# WatchDog.net
KiCad netlist of a schematic drawn in EAGLE
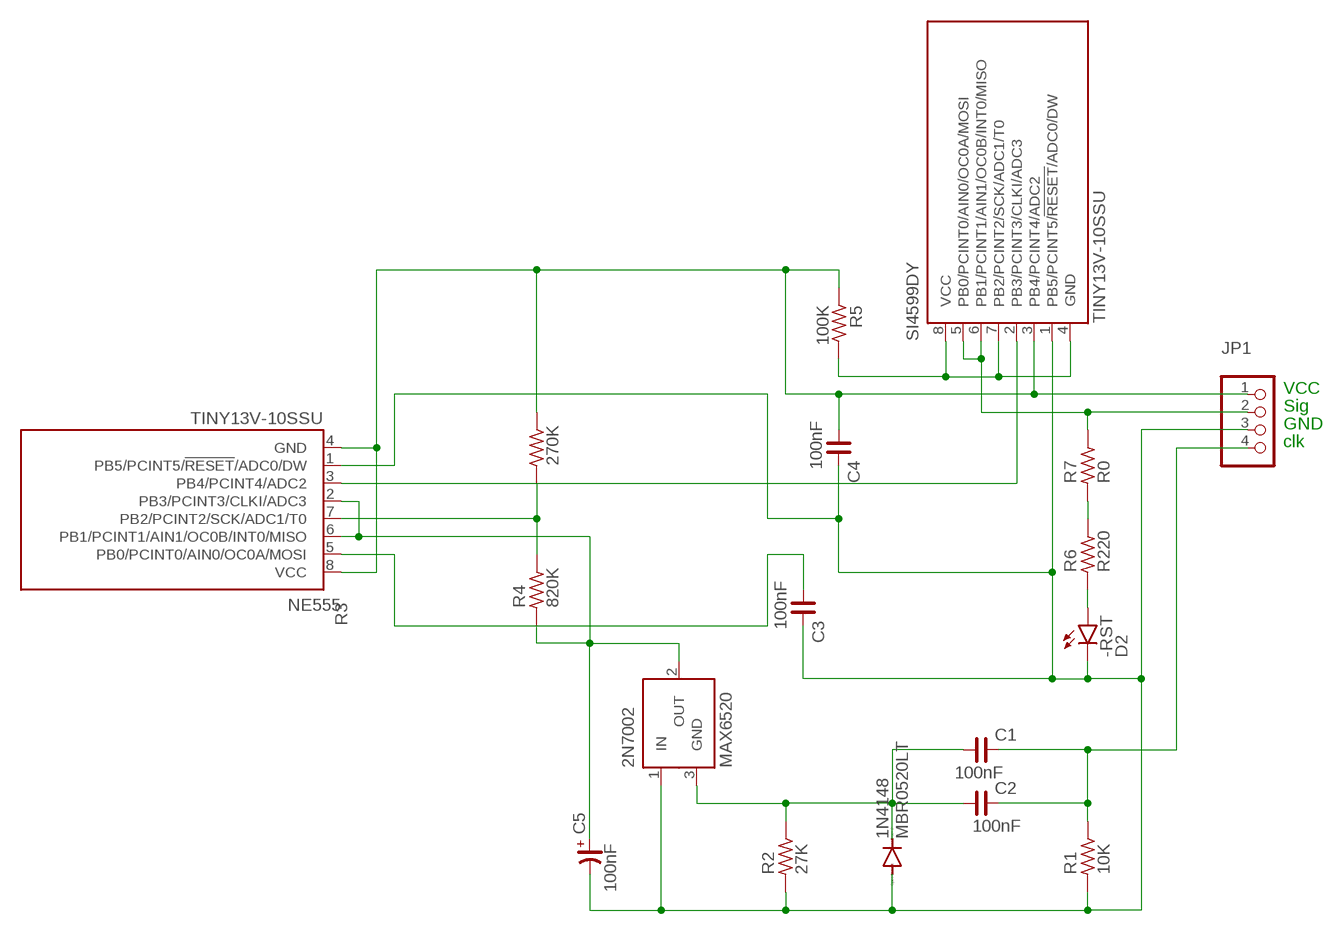
[diagram p0: schematic, sheet 1]

(export (version "E")
  (design (tool "Eeschema 10.0.6"))
  (components
    (comp (ref "-RST")
      (value "D2")
      (footprint "eagle-import:SML0603")
      (libsource (lib "eagle-import") (part "LEDSML0603"))
    )
    (comp (ref "1N4148")
      (value "MBR0520LT")
      (footprint "eagle-import:SOD123")
      (libsource (lib "eagle-import") (part "MBR0520LT"))
    )
    (comp (ref "2N7002")
      (value "MAX6520")
      (footprint "eagle-import:SOT23")
      (fields (field (name "MF") "MAXIM") (field (name "MPN") "MAX6520EUR-T"))
      (libsource (lib "eagle-import") (part "MAX6520"))
    )
    (comp (ref "C1")
      (value "100nF")
      (footprint "eagle-import:C0603")
      (libsource (lib "eagle-import") (part "C_0603"))
    )
    (comp (ref "C2")
      (value "100nF")
      (footprint "eagle-import:C0603")
      (libsource (lib "eagle-import") (part "C_0603"))
    )
    (comp (ref "C3")
      (value "100nF")
      (footprint "eagle-import:C0603")
      (libsource (lib "eagle-import") (part "C_0603"))
    )
    (comp (ref "C4")
      (value "100nF")
      (footprint "eagle-import:C0603")
      (libsource (lib "eagle-import") (part "C_0603"))
    )
    (comp (ref "C5")
      (value "100nF")
      (footprint "eagle-import:CSV-E_F")
      (libsource (lib "eagle-import") (part "CP_SV-E/F"))
    )
    (comp (ref "JP1")
      (value "PINHD-1X4")
      (footprint "eagle-import:1X04")
      (libsource (lib "eagle-import") (part "PINHD-1X4"))
    )
    (comp (ref "NE555")
      (value "TINY13V-10SSU")
      (footprint "eagle-import:8S1")
      (fields (field (name "MPN") "ATTINY13V-10SSU"))
      (libsource (lib "eagle-import") (part "TINY13SSUV-10"))
    )
    (comp (ref "R1")
      (value "10K")
      (footprint "eagle-import:R0603")
      (libsource (lib "eagle-import") (part "R_0603"))
    )
    (comp (ref "R2")
      (value "27K")
      (footprint "eagle-import:R0603")
      (libsource (lib "eagle-import") (part "R_0603"))
    )
    (comp (ref "R3")
      (value "270K")
      (footprint "eagle-import:R0603")
      (libsource (lib "eagle-import") (part "R_0603"))
    )
    (comp (ref "R4")
      (value "820K")
      (footprint "eagle-import:R0603")
      (libsource (lib "eagle-import") (part "R_0603"))
    )
    (comp (ref "R5")
      (value "100K")
      (footprint "eagle-import:R0603")
      (libsource (lib "eagle-import") (part "R_0603"))
    )
    (comp (ref "R6")
      (value "R220")
      (footprint "eagle-import:R0603")
      (libsource (lib "eagle-import") (part "R_0603"))
    )
    (comp (ref "R7")
      (value "R0")
      (footprint "eagle-import:R0402")
      (libsource (lib "eagle-import") (part "R_0402"))
    )
    (comp (ref "SI4599DY")
      (value "TINY13V-10SSU")
      (footprint "eagle-import:8S1")
      (fields (field (name "MPN") "ATTINY13V-10SSU"))
      (libsource (lib "eagle-import") (part "TINY13SSUV-10"))
    )
  )
  (nets
    (net (code "1") (name "Net-(-RST-PadA)") (class "Default")
      (node (ref "-RST") (pin "A") (pinfunction "A_A") (pintype "passive"))
      (node (ref "R6") (pin "1") (pinfunction "1_1") (pintype "passive"))
    )
    (net (code "2") (name "Net-(2N7002-GND)") (class "Default")
      (node (ref "1N4148") (pin "C") (pinfunction "C_C") (pintype "passive"))
      (node (ref "2N7002") (pin "3") (pinfunction "GND_3") (pintype "power_in"))
      (node (ref "C1") (pin "1") (pinfunction "1_1") (pintype "passive"))
      (node (ref "C2") (pin "1") (pinfunction "1_1") (pintype "passive"))
      (node (ref "R2") (pin "2") (pinfunction "2_2") (pintype "passive"))
    )
    (net (code "3") (name "Net-(2N7002-IN)") (class "Default")
      (node (ref "-RST") (pin "C") (pinfunction "C_C") (pintype "passive"))
      (node (ref "1N4148") (pin "A") (pinfunction "A_A") (pintype "passive"))
      (node (ref "2N7002") (pin "1") (pinfunction "IN_1") (pintype "input"))
      (node (ref "C3") (pin "2") (pinfunction "2_2") (pintype "passive"))
      (node (ref "C4") (pin "2") (pinfunction "2_2") (pintype "passive"))
      (node (ref "C5") (pin "-") (pinfunction "-_-") (pintype "passive"))
      (node (ref "JP1") (pin "3") (pinfunction "3_3") (pintype "passive"))
      (node (ref "NE555") (pin "1") (pinfunction "PB5/PCINT5/~{RESET}/ADC0/DW_1") (pintype "bidirectional"))
      (node (ref "R1") (pin "1") (pinfunction "1_1") (pintype "passive"))
      (node (ref "R2") (pin "1") (pinfunction "1_1") (pintype "passive"))
      (node (ref "SI4599DY") (pin "1") (pinfunction "PB5/PCINT5/~{RESET}/ADC0/DW_1") (pintype "bidirectional"))
    )
    (net (code "4") (name "Net-(2N7002-OUT)") (class "Default")
      (node (ref "2N7002") (pin "2") (pinfunction "OUT_2") (pintype "output"))
      (node (ref "C5") (pin "+") (pinfunction "+_+") (pintype "passive"))
      (node (ref "NE555") (pin "2") (pinfunction "PB3/PCINT3/CLKI/ADC3_2") (pintype "bidirectional"))
      (node (ref "NE555") (pin "6") (pinfunction "PB1/PCINT1/AIN1/OC0B/INT0/MISO_6") (pintype "bidirectional"))
      (node (ref "R4") (pin "1") (pinfunction "1_1") (pintype "passive"))
    )
    (net (code "5") (name "Net-(C1-Pad2)") (class "Default")
      (node (ref "C1") (pin "2") (pinfunction "2_2") (pintype "passive"))
      (node (ref "C2") (pin "2") (pinfunction "2_2") (pintype "passive"))
      (node (ref "JP1") (pin "4") (pinfunction "4_4") (pintype "passive"))
      (node (ref "R1") (pin "2") (pinfunction "2_2") (pintype "passive"))
    )
    (net (code "6") (name "Net-(NE555-GND)") (class "Default")
      (node (ref "C4") (pin "1") (pinfunction "1_1") (pintype "passive"))
      (node (ref "JP1") (pin "1") (pinfunction "1_1") (pintype "passive"))
      (node (ref "NE555") (pin "4") (pinfunction "GND_4") (pintype "power_in"))
      (node (ref "NE555") (pin "8") (pinfunction "VCC_8") (pintype "power_in"))
      (node (ref "R3") (pin "2") (pinfunction "2_2") (pintype "passive"))
      (node (ref "R5") (pin "1") (pinfunction "1_1") (pintype "passive"))
      (node (ref "SI4599DY") (pin "3") (pinfunction "PB4/PCINT4/ADC2_3") (pintype "bidirectional"))
    )
    (net (code "7") (name "Net-(NE555-PB0{slash}PCINT0{slash}AIN0{slash}OC0A{slash}MOSI)") (class "Default")
      (node (ref "C3") (pin "1") (pinfunction "1_1") (pintype "passive"))
      (node (ref "NE555") (pin "5") (pinfunction "PB0/PCINT0/AIN0/OC0A/MOSI_5") (pintype "bidirectional"))
    )
    (net (code "8") (name "Net-(NE555-PB2{slash}PCINT2{slash}SCK{slash}ADC1{slash}T0)") (class "Default")
      (node (ref "NE555") (pin "7") (pinfunction "PB2/PCINT2/SCK/ADC1/T0_7") (pintype "bidirectional"))
      (node (ref "R3") (pin "1") (pinfunction "1_1") (pintype "passive"))
      (node (ref "R4") (pin "2") (pinfunction "2_2") (pintype "passive"))
    )
    (net (code "9") (name "Net-(NE555-PB4{slash}PCINT4{slash}ADC2)") (class "Default")
      (node (ref "NE555") (pin "3") (pinfunction "PB4/PCINT4/ADC2_3") (pintype "bidirectional"))
      (node (ref "SI4599DY") (pin "2") (pinfunction "PB3/PCINT3/CLKI/ADC3_2") (pintype "bidirectional"))
    )
    (net (code "10") (name "Net-(R6-Pad2)") (class "Default")
      (node (ref "R6") (pin "2") (pinfunction "2_2") (pintype "passive"))
      (node (ref "R7") (pin "1") (pinfunction "1_1") (pintype "passive"))
    )
    (net (code "11") (name "Net-(SI4599DY-GND)") (class "Default")
      (node (ref "R5") (pin "2") (pinfunction "2_2") (pintype "passive"))
      (node (ref "SI4599DY") (pin "4") (pinfunction "GND_4") (pintype "power_in"))
      (node (ref "SI4599DY") (pin "7") (pinfunction "PB2/PCINT2/SCK/ADC1/T0_7") (pintype "bidirectional"))
      (node (ref "SI4599DY") (pin "8") (pinfunction "VCC_8") (pintype "power_in"))
    )
    (net (code "12") (name "Net-(SI4599DY-PB0{slash}PCINT0{slash}AIN0{slash}OC0A{slash}MOSI)") (class "Default")
      (node (ref "JP1") (pin "2") (pinfunction "2_2") (pintype "passive"))
      (node (ref "R7") (pin "2") (pinfunction "2_2") (pintype "passive"))
      (node (ref "SI4599DY") (pin "5") (pinfunction "PB0/PCINT0/AIN0/OC0A/MOSI_5") (pintype "bidirectional"))
      (node (ref "SI4599DY") (pin "6") (pinfunction "PB1/PCINT1/AIN1/OC0B/INT0/MISO_6") (pintype "bidirectional"))
    )
  )
)
